# 04ddr3.net
KiCad netlist of a schematic drawn in Altium Designer
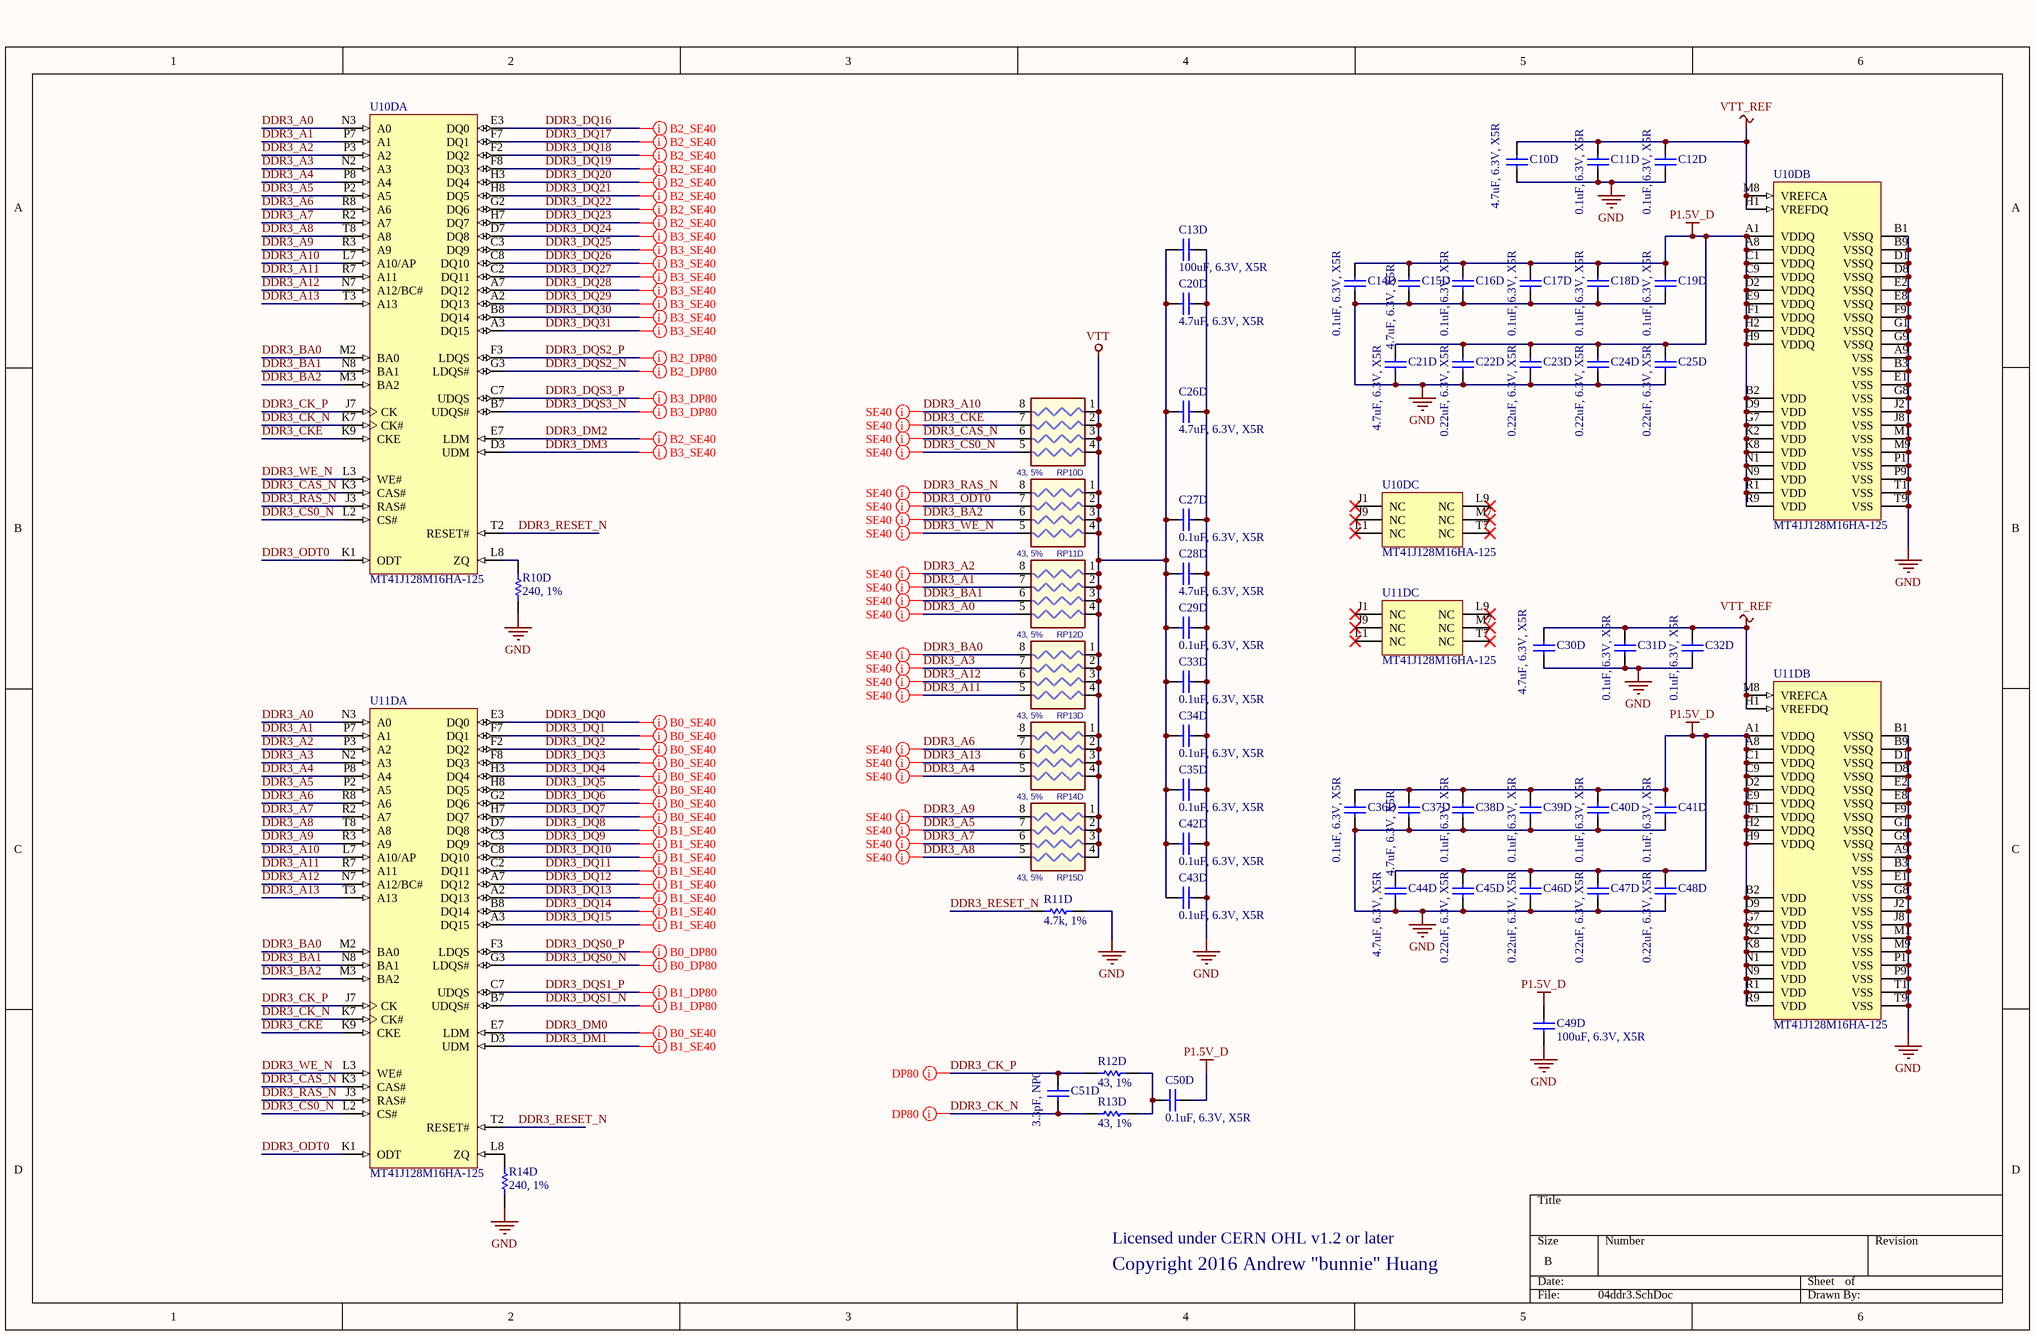
[diagram p0: 04ddr3.SchDoc]

(export (version "E")
  (design (tool "Eeschema 10.0.6"))
  (components
    (comp (ref "C10D")
      (value "4.7uF, 6.3V, X5R")
      (footprint "CAPC1005N")
      (description "Capacitor (Semiconductor SIM Model)")
      (fields (field (name "MPN") "CL05A475MQ5NQNC"))
      (libsource (lib "Miscellaneous Devices") (part "Cap Semi"))
    )
    (comp (ref "C11D")
      (value "0.1uF, 6.3V, X5R")
      (footprint "CAPC0603X03L")
      (description "Capacitor (Semiconductor SIM Model)")
      (fields (field (name "MPN") "CL03A104KQ3NNNC"))
      (libsource (lib "Miscellaneous Devices") (part "Cap Semi"))
    )
    (comp (ref "C12D")
      (value "0.1uF, 6.3V, X5R")
      (footprint "CAPC0603X03L")
      (description "Capacitor (Semiconductor SIM Model)")
      (fields (field (name "MPN") "CL03A104KQ3NNNC"))
      (libsource (lib "Miscellaneous Devices") (part "Cap Semi"))
    )
    (comp (ref "C13D")
      (value "100uF, 6.3V, X5R")
      (footprint "CAPC3216N")
      (description "Capacitor (Semiconductor SIM Model)")
      (fields (field (name "MPN") "CL31A107MQHNNNE"))
      (libsource (lib "Miscellaneous Devices") (part "Cap Semi"))
    )
    (comp (ref "C14D")
      (value "0.1uF, 6.3V, X5R")
      (footprint "CAPC0603X03L")
      (description "Capacitor (Semiconductor SIM Model)")
      (fields (field (name "MPN") "CL03A104KQ3NNNC"))
      (libsource (lib "Miscellaneous Devices") (part "Cap Semi"))
    )
    (comp (ref "C15D")
      (value "4.7uF, 6.3V, X5R")
      (footprint "CAPC1005N")
      (description "Capacitor (Semiconductor SIM Model)")
      (fields (field (name "MPN") "CL05A475MQ5NQNC"))
      (libsource (lib "Miscellaneous Devices") (part "Cap Semi"))
    )
    (comp (ref "C16D")
      (value "0.1uF, 6.3V, X5R")
      (footprint "CAPC0603X03L")
      (description "Capacitor (Semiconductor SIM Model)")
      (fields (field (name "MPN") "CL03A104KQ3NNNC"))
      (libsource (lib "Miscellaneous Devices") (part "Cap Semi"))
    )
    (comp (ref "C17D")
      (value "0.1uF, 6.3V, X5R")
      (footprint "CAPC0603X03L")
      (description "Capacitor (Semiconductor SIM Model)")
      (fields (field (name "MPN") "CL03A104KQ3NNNC"))
      (libsource (lib "Miscellaneous Devices") (part "Cap Semi"))
    )
    (comp (ref "C18D")
      (value "0.1uF, 6.3V, X5R")
      (footprint "CAPC0603X03L")
      (description "Capacitor (Semiconductor SIM Model)")
      (fields (field (name "MPN") "CL03A104KQ3NNNC"))
      (libsource (lib "Miscellaneous Devices") (part "Cap Semi"))
    )
    (comp (ref "C19D")
      (value "0.1uF, 6.3V, X5R")
      (footprint "CAPC0603X03L")
      (description "Capacitor (Semiconductor SIM Model)")
      (fields (field (name "MPN") "CL03A104KQ3NNNC"))
      (libsource (lib "Miscellaneous Devices") (part "Cap Semi"))
    )
    (comp (ref "C20D")
      (value "4.7uF, 6.3V, X5R")
      (footprint "CAPC1005N")
      (description "Capacitor (Semiconductor SIM Model)")
      (fields (field (name "MPN") "CL05A475MQ5NQNC"))
      (libsource (lib "Miscellaneous Devices") (part "Cap Semi"))
    )
    (comp (ref "C21D")
      (value "4.7uF, 6.3V, X5R")
      (footprint "CAPC1005N")
      (description "Capacitor (Semiconductor SIM Model)")
      (fields (field (name "MPN") "CL05A475MQ5NQNC"))
      (libsource (lib "Miscellaneous Devices") (part "Cap Semi"))
    )
    (comp (ref "C22D")
      (value "0.22uF, 6.3V, X5R")
      (footprint "CAPC0603X03L")
      (description "Capacitor (Semiconductor SIM Model)")
      (fields (field (name "MPN") "CL03A224MQ3NNNC"))
      (libsource (lib "Miscellaneous Devices") (part "Cap Semi"))
    )
    (comp (ref "C23D")
      (value "0.22uF, 6.3V, X5R")
      (footprint "CAPC0603X03L")
      (description "Capacitor (Semiconductor SIM Model)")
      (fields (field (name "MPN") "CL03A224MQ3NNNC"))
      (libsource (lib "Miscellaneous Devices") (part "Cap Semi"))
    )
    (comp (ref "C24D")
      (value "0.22uF, 6.3V, X5R")
      (footprint "CAPC0603X03L")
      (description "Capacitor (Semiconductor SIM Model)")
      (fields (field (name "MPN") "CL03A224MQ3NNNC"))
      (libsource (lib "Miscellaneous Devices") (part "Cap Semi"))
    )
    (comp (ref "C25D")
      (value "0.22uF, 6.3V, X5R")
      (footprint "CAPC0603X03L")
      (description "Capacitor (Semiconductor SIM Model)")
      (fields (field (name "MPN") "CL03A224MQ3NNNC"))
      (libsource (lib "Miscellaneous Devices") (part "Cap Semi"))
    )
    (comp (ref "C26D")
      (value "4.7uF, 6.3V, X5R")
      (footprint "CAPC1005N")
      (description "Capacitor (Semiconductor SIM Model)")
      (fields (field (name "MPN") "CL05A475MQ5NQNC"))
      (libsource (lib "Miscellaneous Devices") (part "Cap Semi"))
    )
    (comp (ref "C27D")
      (value "0.1uF, 6.3V, X5R")
      (footprint "CAPC0603X03L")
      (description "Capacitor (Semiconductor SIM Model)")
      (fields (field (name "MPN") "CL03A104KQ3NNNC"))
      (libsource (lib "Miscellaneous Devices") (part "Cap Semi"))
    )
    (comp (ref "C28D")
      (value "4.7uF, 6.3V, X5R")
      (footprint "CAPC1005N")
      (description "Capacitor (Semiconductor SIM Model)")
      (fields (field (name "MPN") "CL05A475MQ5NQNC"))
      (libsource (lib "Miscellaneous Devices") (part "Cap Semi"))
    )
    (comp (ref "C29D")
      (value "0.1uF, 6.3V, X5R")
      (footprint "CAPC0603X03L")
      (description "Capacitor (Semiconductor SIM Model)")
      (fields (field (name "MPN") "CL03A104KQ3NNNC"))
      (libsource (lib "Miscellaneous Devices") (part "Cap Semi"))
    )
    (comp (ref "C30D")
      (value "4.7uF, 6.3V, X5R")
      (footprint "CAPC1005N")
      (description "Capacitor (Semiconductor SIM Model)")
      (fields (field (name "MPN") "CL05A475MQ5NQNC"))
      (libsource (lib "Miscellaneous Devices") (part "Cap Semi"))
    )
    (comp (ref "C31D")
      (value "0.1uF, 6.3V, X5R")
      (footprint "CAPC0603X03L")
      (description "Capacitor (Semiconductor SIM Model)")
      (fields (field (name "MPN") "CL03A104KQ3NNNC"))
      (libsource (lib "Miscellaneous Devices") (part "Cap Semi"))
    )
    (comp (ref "C32D")
      (value "0.1uF, 6.3V, X5R")
      (footprint "CAPC0603X03L")
      (description "Capacitor (Semiconductor SIM Model)")
      (fields (field (name "MPN") "CL03A104KQ3NNNC"))
      (libsource (lib "Miscellaneous Devices") (part "Cap Semi"))
    )
    (comp (ref "C33D")
      (value "0.1uF, 6.3V, X5R")
      (footprint "CAPC0603X03L")
      (description "Capacitor (Semiconductor SIM Model)")
      (fields (field (name "MPN") "CL03A104KQ3NNNC"))
      (libsource (lib "Miscellaneous Devices") (part "Cap Semi"))
    )
    (comp (ref "C34D")
      (value "0.1uF, 6.3V, X5R")
      (footprint "CAPC0603X03L")
      (description "Capacitor (Semiconductor SIM Model)")
      (fields (field (name "MPN") "CL03A104KQ3NNNC"))
      (libsource (lib "Miscellaneous Devices") (part "Cap Semi"))
    )
    (comp (ref "C35D")
      (value "0.1uF, 6.3V, X5R")
      (footprint "CAPC0603X03L")
      (description "Capacitor (Semiconductor SIM Model)")
      (fields (field (name "MPN") "CL03A104KQ3NNNC"))
      (libsource (lib "Miscellaneous Devices") (part "Cap Semi"))
    )
    (comp (ref "C36D")
      (value "0.1uF, 6.3V, X5R")
      (footprint "CAPC0603X03L")
      (description "Capacitor (Semiconductor SIM Model)")
      (fields (field (name "MPN") "CL03A104KQ3NNNC"))
      (libsource (lib "Miscellaneous Devices") (part "Cap Semi"))
    )
    (comp (ref "C37D")
      (value "4.7uF, 6.3V, X5R")
      (footprint "CAPC1005N")
      (description "Capacitor (Semiconductor SIM Model)")
      (fields (field (name "MPN") "CL05A475MQ5NQNC"))
      (libsource (lib "Miscellaneous Devices") (part "Cap Semi"))
    )
    (comp (ref "C38D")
      (value "0.1uF, 6.3V, X5R")
      (footprint "CAPC0603X03L")
      (description "Capacitor (Semiconductor SIM Model)")
      (fields (field (name "MPN") "CL03A104KQ3NNNC"))
      (libsource (lib "Miscellaneous Devices") (part "Cap Semi"))
    )
    (comp (ref "C39D")
      (value "0.1uF, 6.3V, X5R")
      (footprint "CAPC0603X03L")
      (description "Capacitor (Semiconductor SIM Model)")
      (fields (field (name "MPN") "CL03A104KQ3NNNC"))
      (libsource (lib "Miscellaneous Devices") (part "Cap Semi"))
    )
    (comp (ref "C40D")
      (value "0.1uF, 6.3V, X5R")
      (footprint "CAPC0603X03L")
      (description "Capacitor (Semiconductor SIM Model)")
      (fields (field (name "MPN") "CL03A104KQ3NNNC"))
      (libsource (lib "Miscellaneous Devices") (part "Cap Semi"))
    )
    (comp (ref "C41D")
      (value "0.1uF, 6.3V, X5R")
      (footprint "CAPC0603X03L")
      (description "Capacitor (Semiconductor SIM Model)")
      (fields (field (name "MPN") "CL03A104KQ3NNNC"))
      (libsource (lib "Miscellaneous Devices") (part "Cap Semi"))
    )
    (comp (ref "C42D")
      (value "0.1uF, 6.3V, X5R")
      (footprint "CAPC0603X03L")
      (description "Capacitor (Semiconductor SIM Model)")
      (fields (field (name "MPN") "CL03A104KQ3NNNC"))
      (libsource (lib "Miscellaneous Devices") (part "Cap Semi"))
    )
    (comp (ref "C43D")
      (value "0.1uF, 6.3V, X5R")
      (footprint "CAPC0603X03L")
      (description "Capacitor (Semiconductor SIM Model)")
      (fields (field (name "MPN") "CL03A104KQ3NNNC"))
      (libsource (lib "Miscellaneous Devices") (part "Cap Semi"))
    )
    (comp (ref "C44D")
      (value "4.7uF, 6.3V, X5R")
      (footprint "CAPC1005N")
      (description "Capacitor (Semiconductor SIM Model)")
      (fields (field (name "MPN") "CL05A475MQ5NQNC"))
      (libsource (lib "Miscellaneous Devices") (part "Cap Semi"))
    )
    (comp (ref "C45D")
      (value "0.22uF, 6.3V, X5R")
      (footprint "CAPC0603X03L")
      (description "Capacitor (Semiconductor SIM Model)")
      (fields (field (name "MPN") "CL03A224MQ3NNNC"))
      (libsource (lib "Miscellaneous Devices") (part "Cap Semi"))
    )
    (comp (ref "C46D")
      (value "0.22uF, 6.3V, X5R")
      (footprint "CAPC0603X03L")
      (description "Capacitor (Semiconductor SIM Model)")
      (fields (field (name "MPN") "CL03A224MQ3NNNC"))
      (libsource (lib "Miscellaneous Devices") (part "Cap Semi"))
    )
    (comp (ref "C47D")
      (value "0.22uF, 6.3V, X5R")
      (footprint "CAPC0603X03L")
      (description "Capacitor (Semiconductor SIM Model)")
      (fields (field (name "MPN") "CL03A224MQ3NNNC"))
      (libsource (lib "Miscellaneous Devices") (part "Cap Semi"))
    )
    (comp (ref "C48D")
      (value "0.22uF, 6.3V, X5R")
      (footprint "CAPC0603X03L")
      (description "Capacitor (Semiconductor SIM Model)")
      (fields (field (name "MPN") "CL03A224MQ3NNNC"))
      (libsource (lib "Miscellaneous Devices") (part "Cap Semi"))
    )
    (comp (ref "C49D")
      (value "100uF, 6.3V, X5R")
      (footprint "CAPC3216N")
      (description "Capacitor (Semiconductor SIM Model)")
      (fields (field (name "MPN") "CL31A107MQHNNNE"))
      (libsource (lib "Miscellaneous Devices") (part "Cap Semi"))
    )
    (comp (ref "C50D")
      (value "0.1uF, 6.3V, X5R")
      (footprint "CAPC0603X03L")
      (description "Capacitor (Semiconductor SIM Model)")
      (fields (field (name "MPN") "CL03A104KQ3NNNC"))
      (libsource (lib "Miscellaneous Devices") (part "Cap Semi"))
    )
    (comp (ref "C51D")
      (value "3.3pF, NP0")
      (footprint "CAPC0603X03L")
      (description "Capacitor (Semiconductor SIM Model)")
      (fields (field (name "MPN") "GRM0335C1H3R3CA01D"))
      (libsource (lib "Miscellaneous Devices") (part "Cap Semi"))
    )
    (comp (ref "R10D")
      (value "240, 1%")
      (footprint "CAPC0603X03L")
      (description "Resistor")
      (fields (field (name "MPN") "ANY"))
      (libsource (lib "Miscellaneous Devices") (part "Res1"))
    )
    (comp (ref "R11D")
      (value "4.7k, 1%")
      (footprint "RESC1005N")
      (description "Resistor")
      (fields (field (name "MPN") "ANY"))
      (libsource (lib "Miscellaneous Devices") (part "Res1"))
    )
    (comp (ref "R12D")
      (value "43, 1%")
      (footprint "RESC1005N")
      (description "Resistor")
      (fields (field (name "MPN") "ANY"))
      (libsource (lib "Miscellaneous Devices") (part "Res1"))
    )
    (comp (ref "R13D")
      (value "43, 1%")
      (footprint "RESC1005N")
      (description "Resistor")
      (fields (field (name "MPN") "ANY"))
      (libsource (lib "Miscellaneous Devices") (part "Res1"))
    )
    (comp (ref "R14D")
      (value "240, 1%")
      (footprint "CAPC0603X03L")
      (description "Resistor")
      (fields (field (name "MPN") "ANY"))
      (libsource (lib "Miscellaneous Devices") (part "Res1"))
    )
    (comp (ref "RP10D")
      (value "43, 5%")
      (fields (field (name "MPN") "RP104PJ430CS"))
      (libsource (lib "*") (part "RPACK4"))
    )
    (comp (ref "RP11D")
      (value "43, 5%")
      (fields (field (name "MPN") "RP104PJ430CS"))
      (libsource (lib "*") (part "RPACK4"))
    )
    (comp (ref "RP12D")
      (value "43, 5%")
      (fields (field (name "MPN") "RP104PJ430CS"))
      (libsource (lib "*") (part "RPACK4"))
    )
    (comp (ref "RP13D")
      (value "43, 5%")
      (fields (field (name "MPN") "RP104PJ430CS"))
      (libsource (lib "*") (part "RPACK4"))
    )
    (comp (ref "RP14D")
      (value "43, 5%")
      (fields (field (name "MPN") "RP104PJ430CS"))
      (libsource (lib "*") (part "RPACK4"))
    )
    (comp (ref "RP15D")
      (value "43, 5%")
      (fields (field (name "MPN") "RP104PJ430CS"))
      (libsource (lib "*") (part "RPACK4"))
    )
    (comp (ref "U10D")
      (value "MT41J128M16HA-125")
      (footprint "MICT-HA-96")
      (description "2Gb DDR3-1600 SDRAM, 128Mb x 16, 1.25ns, 1.5V, 0 to 95 degC, 96-Ball FBGA, Pb-Free")
      (fields (field (name "VOLTAGE") "1.5V ") (field (name "MPN") "MT41J128M16JT-125:K"))
      (libsource (lib "Micron Memory DDR3 SDRAM") (part "MT41J128M16HA-125"))
    )
    (comp (ref "U11D")
      (value "MT41J128M16HA-125")
      (footprint "MICT-HA-96")
      (description "2Gb DDR3-1600 SDRAM, 128Mb x 16, 1.25ns, 1.5V, 0 to 95 degC, 96-Ball FBGA, Pb-Free")
      (fields (field (name "VOLTAGE") "1.5V ") (field (name "MPN") "MT41J128M16JT-125:K"))
      (libsource (lib "Micron Memory DDR3 SDRAM") (part "MT41J128M16HA-125"))
    )
  )
  (nets
    (net (code "1") (name "/DDR3_A0") (class "Default")
      (node (ref "RP12D") (pin "5") (pinfunction "R42_5") (pintype "passive"))
      (node (ref "U10D") (pin "N3") (pinfunction "A0_N3") (pintype "input"))
      (node (ref "U11D") (pin "N3") (pinfunction "A0_N3") (pintype "input"))
    )
    (net (code "2") (name "/DDR3_A1") (class "Default")
      (node (ref "RP12D") (pin "7") (pinfunction "R22_7") (pintype "passive"))
      (node (ref "U10D") (pin "P7") (pinfunction "A1_P7") (pintype "input"))
      (node (ref "U11D") (pin "P7") (pinfunction "A1_P7") (pintype "input"))
    )
    (net (code "3") (name "/DDR3_A2") (class "Default")
      (node (ref "RP12D") (pin "8") (pinfunction "R12_8") (pintype "passive"))
      (node (ref "U10D") (pin "P3") (pinfunction "A2_P3") (pintype "input"))
      (node (ref "U11D") (pin "P3") (pinfunction "A2_P3") (pintype "input"))
    )
    (net (code "4") (name "/DDR3_A3") (class "Default")
      (node (ref "RP13D") (pin "7") (pinfunction "R22_7") (pintype "passive"))
      (node (ref "U10D") (pin "N2") (pinfunction "A3_N2") (pintype "input"))
      (node (ref "U11D") (pin "N2") (pinfunction "A3_N2") (pintype "input"))
    )
    (net (code "5") (name "/DDR3_A4") (class "Default")
      (node (ref "RP14D") (pin "5") (pinfunction "R42_5") (pintype "passive"))
      (node (ref "U10D") (pin "P8") (pinfunction "A4_P8") (pintype "input"))
      (node (ref "U11D") (pin "P8") (pinfunction "A4_P8") (pintype "input"))
    )
    (net (code "6") (name "/DDR3_A5") (class "Default")
      (node (ref "RP15D") (pin "7") (pinfunction "R22_7") (pintype "passive"))
      (node (ref "U10D") (pin "P2") (pinfunction "A5_P2") (pintype "input"))
      (node (ref "U11D") (pin "P2") (pinfunction "A5_P2") (pintype "input"))
    )
    (net (code "7") (name "/DDR3_A6") (class "Default")
      (node (ref "RP14D") (pin "7") (pinfunction "R22_7") (pintype "passive"))
      (node (ref "U10D") (pin "R8") (pinfunction "A6_R8") (pintype "input"))
      (node (ref "U11D") (pin "R8") (pinfunction "A6_R8") (pintype "input"))
    )
    (net (code "8") (name "/DDR3_A7") (class "Default")
      (node (ref "RP15D") (pin "6") (pinfunction "R32_6") (pintype "passive"))
      (node (ref "U10D") (pin "R2") (pinfunction "A7_R2") (pintype "input"))
      (node (ref "U11D") (pin "R2") (pinfunction "A7_R2") (pintype "input"))
    )
    (net (code "9") (name "/DDR3_A8") (class "Default")
      (node (ref "RP15D") (pin "5") (pinfunction "R42_5") (pintype "passive"))
      (node (ref "U10D") (pin "T8") (pinfunction "A8_T8") (pintype "input"))
      (node (ref "U11D") (pin "T8") (pinfunction "A8_T8") (pintype "input"))
    )
    (net (code "10") (name "/DDR3_A9") (class "Default")
      (node (ref "RP15D") (pin "8") (pinfunction "R12_8") (pintype "passive"))
      (node (ref "U10D") (pin "R3") (pinfunction "A9_R3") (pintype "input"))
      (node (ref "U11D") (pin "R3") (pinfunction "A9_R3") (pintype "input"))
    )
    (net (code "11") (name "/DDR3_A10") (class "Default")
      (node (ref "RP10D") (pin "8") (pinfunction "R12_8") (pintype "passive"))
      (node (ref "U10D") (pin "L7") (pinfunction "A10/AP_L7") (pintype "input"))
      (node (ref "U11D") (pin "L7") (pinfunction "A10/AP_L7") (pintype "input"))
    )
    (net (code "12") (name "/DDR3_A11") (class "Default")
      (node (ref "RP13D") (pin "5") (pinfunction "R42_5") (pintype "passive"))
      (node (ref "U10D") (pin "R7") (pinfunction "A11_R7") (pintype "input"))
      (node (ref "U11D") (pin "R7") (pinfunction "A11_R7") (pintype "input"))
    )
    (net (code "13") (name "/DDR3_A12") (class "Default")
      (node (ref "RP13D") (pin "6") (pinfunction "R32_6") (pintype "passive"))
      (node (ref "U10D") (pin "N7") (pinfunction "A12/BC#_N7") (pintype "input"))
      (node (ref "U11D") (pin "N7") (pinfunction "A12/BC#_N7") (pintype "input"))
    )
    (net (code "14") (name "/DDR3_A13") (class "Default")
      (node (ref "RP14D") (pin "6") (pinfunction "R32_6") (pintype "passive"))
      (node (ref "U10D") (pin "T3") (pinfunction "A13_T3") (pintype "input"))
      (node (ref "U11D") (pin "T3") (pinfunction "A13_T3") (pintype "input"))
    )
    (net (code "15") (name "/DDR3_BA0") (class "Default")
      (node (ref "RP13D") (pin "8") (pinfunction "R12_8") (pintype "passive"))
      (node (ref "U10D") (pin "M2") (pinfunction "BA0_M2") (pintype "input"))
      (node (ref "U11D") (pin "M2") (pinfunction "BA0_M2") (pintype "input"))
    )
    (net (code "16") (name "/DDR3_BA1") (class "Default")
      (node (ref "RP12D") (pin "6") (pinfunction "R32_6") (pintype "passive"))
      (node (ref "U10D") (pin "N8") (pinfunction "BA1_N8") (pintype "input"))
      (node (ref "U11D") (pin "N8") (pinfunction "BA1_N8") (pintype "input"))
    )
    (net (code "17") (name "/DDR3_BA2") (class "Default")
      (node (ref "RP11D") (pin "6") (pinfunction "R32_6") (pintype "passive"))
      (node (ref "U10D") (pin "M3") (pinfunction "BA2_M3") (pintype "input"))
      (node (ref "U11D") (pin "M3") (pinfunction "BA2_M3") (pintype "input"))
    )
    (net (code "18") (name "/DDR3_CAS_N") (class "Default")
      (node (ref "RP10D") (pin "6") (pinfunction "R32_6") (pintype "passive"))
      (node (ref "U10D") (pin "K3") (pinfunction "CAS#_K3") (pintype "input"))
      (node (ref "U11D") (pin "K3") (pinfunction "CAS#_K3") (pintype "input"))
    )
    (net (code "19") (name "/DDR3_CKE") (class "Default")
      (node (ref "RP10D") (pin "7") (pinfunction "R22_7") (pintype "passive"))
      (node (ref "U10D") (pin "K9") (pinfunction "CKE_K9") (pintype "input"))
      (node (ref "U11D") (pin "K9") (pinfunction "CKE_K9") (pintype "input"))
    )
    (net (code "20") (name "/DDR3_CK_N") (class "Default")
      (node (ref "C51D") (pin "1") (pinfunction "1_1") (pintype "passive"))
      (node (ref "R13D") (pin "1") (pinfunction "1_1") (pintype "passive"))
      (node (ref "U10D") (pin "K7") (pinfunction "CK#_K7") (pintype "input"))
      (node (ref "U11D") (pin "K7") (pinfunction "CK#_K7") (pintype "input"))
    )
    (net (code "21") (name "/DDR3_CK_P") (class "Default")
      (node (ref "C51D") (pin "2") (pinfunction "2_2") (pintype "passive"))
      (node (ref "R12D") (pin "1") (pinfunction "1_1") (pintype "passive"))
      (node (ref "U10D") (pin "J7") (pinfunction "CK_J7") (pintype "input"))
      (node (ref "U11D") (pin "J7") (pinfunction "CK_J7") (pintype "input"))
    )
    (net (code "22") (name "/DDR3_CS0_N") (class "Default")
      (node (ref "RP10D") (pin "5") (pinfunction "R42_5") (pintype "passive"))
      (node (ref "U10D") (pin "L2") (pinfunction "CS#_L2") (pintype "input"))
      (node (ref "U11D") (pin "L2") (pinfunction "CS#_L2") (pintype "input"))
    )
    (net (code "23") (name "/DDR3_DM0") (class "Default")
      (node (ref "U11D") (pin "E7") (pinfunction "LDM_E7") (pintype "input"))
    )
    (net (code "24") (name "/DDR3_DM1") (class "Default")
      (node (ref "U11D") (pin "D3") (pinfunction "UDM_D3") (pintype "input"))
    )
    (net (code "25") (name "/DDR3_DM2") (class "Default")
      (node (ref "U10D") (pin "E7") (pinfunction "LDM_E7") (pintype "input"))
    )
    (net (code "26") (name "/DDR3_DM3") (class "Default")
      (node (ref "U10D") (pin "D3") (pinfunction "UDM_D3") (pintype "input"))
    )
    (net (code "27") (name "/DDR3_DQ0") (class "Default")
      (node (ref "U11D") (pin "E3") (pinfunction "DQ0_E3") (pintype "bidirectional"))
    )
    (net (code "28") (name "/DDR3_DQ1") (class "Default")
      (node (ref "U11D") (pin "F7") (pinfunction "DQ1_F7") (pintype "bidirectional"))
    )
    (net (code "29") (name "/DDR3_DQ2") (class "Default")
      (node (ref "U11D") (pin "F2") (pinfunction "DQ2_F2") (pintype "bidirectional"))
    )
    (net (code "30") (name "/DDR3_DQ3") (class "Default")
      (node (ref "U11D") (pin "F8") (pinfunction "DQ3_F8") (pintype "bidirectional"))
    )
    (net (code "31") (name "/DDR3_DQ4") (class "Default")
      (node (ref "U11D") (pin "H3") (pinfunction "DQ4_H3") (pintype "bidirectional"))
    )
    (net (code "32") (name "/DDR3_DQ5") (class "Default")
      (node (ref "U11D") (pin "H8") (pinfunction "DQ5_H8") (pintype "bidirectional"))
    )
    (net (code "33") (name "/DDR3_DQ6") (class "Default")
      (node (ref "U11D") (pin "G2") (pinfunction "DQ6_G2") (pintype "bidirectional"))
    )
    (net (code "34") (name "/DDR3_DQ7") (class "Default")
      (node (ref "U11D") (pin "H7") (pinfunction "DQ7_H7") (pintype "bidirectional"))
    )
    (net (code "35") (name "/DDR3_DQ8") (class "Default")
      (node (ref "U11D") (pin "D7") (pinfunction "DQ8_D7") (pintype "bidirectional"))
    )
    (net (code "36") (name "/DDR3_DQ9") (class "Default")
      (node (ref "U11D") (pin "C3") (pinfunction "DQ9_C3") (pintype "bidirectional"))
    )
    (net (code "37") (name "/DDR3_DQ10") (class "Default")
      (node (ref "U11D") (pin "C8") (pinfunction "DQ10_C8") (pintype "bidirectional"))
    )
    (net (code "38") (name "/DDR3_DQ11") (class "Default")
      (node (ref "U11D") (pin "C2") (pinfunction "DQ11_C2") (pintype "bidirectional"))
    )
    (net (code "39") (name "/DDR3_DQ12") (class "Default")
      (node (ref "U11D") (pin "A7") (pinfunction "DQ12_A7") (pintype "bidirectional"))
    )
    (net (code "40") (name "/DDR3_DQ13") (class "Default")
      (node (ref "U11D") (pin "A2") (pinfunction "DQ13_A2") (pintype "bidirectional"))
    )
    (net (code "41") (name "/DDR3_DQ14") (class "Default")
      (node (ref "U11D") (pin "B8") (pinfunction "DQ14_B8") (pintype "bidirectional"))
    )
    (net (code "42") (name "/DDR3_DQ15") (class "Default")
      (node (ref "U11D") (pin "A3") (pinfunction "DQ15_A3") (pintype "bidirectional"))
    )
    (net (code "43") (name "/DDR3_DQ16") (class "Default")
      (node (ref "U10D") (pin "E3") (pinfunction "DQ0_E3") (pintype "bidirectional"))
    )
    (net (code "44") (name "/DDR3_DQ17") (class "Default")
      (node (ref "U10D") (pin "F7") (pinfunction "DQ1_F7") (pintype "bidirectional"))
    )
    (net (code "45") (name "/DDR3_DQ18") (class "Default")
      (node (ref "U10D") (pin "F2") (pinfunction "DQ2_F2") (pintype "bidirectional"))
    )
    (net (code "46") (name "/DDR3_DQ19") (class "Default")
      (node (ref "U10D") (pin "F8") (pinfunction "DQ3_F8") (pintype "bidirectional"))
    )
    (net (code "47") (name "/DDR3_DQ20") (class "Default")
      (node (ref "U10D") (pin "H3") (pinfunction "DQ4_H3") (pintype "bidirectional"))
    )
    (net (code "48") (name "/DDR3_DQ21") (class "Default")
      (node (ref "U10D") (pin "H8") (pinfunction "DQ5_H8") (pintype "bidirectional"))
    )
    (net (code "49") (name "/DDR3_DQ22") (class "Default")
      (node (ref "U10D") (pin "G2") (pinfunction "DQ6_G2") (pintype "bidirectional"))
    )
    (net (code "50") (name "/DDR3_DQ23") (class "Default")
      (node (ref "U10D") (pin "H7") (pinfunction "DQ7_H7") (pintype "bidirectional"))
    )
    (net (code "51") (name "/DDR3_DQ24") (class "Default")
      (node (ref "U10D") (pin "D7") (pinfunction "DQ8_D7") (pintype "bidirectional"))
    )
    (net (code "52") (name "/DDR3_DQ25") (class "Default")
      (node (ref "U10D") (pin "C3") (pinfunction "DQ9_C3") (pintype "bidirectional"))
    )
    (net (code "53") (name "/DDR3_DQ26") (class "Default")
      (node (ref "U10D") (pin "C8") (pinfunction "DQ10_C8") (pintype "bidirectional"))
    )
    (net (code "54") (name "/DDR3_DQ27") (class "Default")
      (node (ref "U10D") (pin "C2") (pinfunction "DQ11_C2") (pintype "bidirectional"))
    )
    (net (code "55") (name "/DDR3_DQ28") (class "Default")
      (node (ref "U10D") (pin "A7") (pinfunction "DQ12_A7") (pintype "bidirectional"))
    )
    (net (code "56") (name "/DDR3_DQ29") (class "Default")
      (node (ref "U10D") (pin "A2") (pinfunction "DQ13_A2") (pintype "bidirectional"))
    )
    (net (code "57") (name "/DDR3_DQ30") (class "Default")
      (node (ref "U10D") (pin "B8") (pinfunction "DQ14_B8") (pintype "bidirectional"))
    )
    (net (code "58") (name "/DDR3_DQ31") (class "Default")
      (node (ref "U10D") (pin "A3") (pinfunction "DQ15_A3") (pintype "bidirectional"))
    )
    (net (code "59") (name "/DDR3_DQS0_N") (class "Default")
      (node (ref "U11D") (pin "G3") (pinfunction "LDQS#_G3") (pintype "bidirectional"))
    )
    (net (code "60") (name "/DDR3_DQS0_P") (class "Default")
      (node (ref "U11D") (pin "F3") (pinfunction "LDQS_F3") (pintype "bidirectional"))
    )
    (net (code "61") (name "/DDR3_DQS1_N") (class "Default")
      (node (ref "U11D") (pin "B7") (pinfunction "UDQS#_B7") (pintype "bidirectional"))
    )
    (net (code "62") (name "/DDR3_DQS1_P") (class "Default")
      (node (ref "U11D") (pin "C7") (pinfunction "UDQS_C7") (pintype "bidirectional"))
    )
    (net (code "63") (name "/DDR3_DQS2_N") (class "Default")
      (node (ref "U10D") (pin "G3") (pinfunction "LDQS#_G3") (pintype "bidirectional"))
    )
    (net (code "64") (name "/DDR3_DQS2_P") (class "Default")
      (node (ref "U10D") (pin "F3") (pinfunction "LDQS_F3") (pintype "bidirectional"))
    )
    (net (code "65") (name "/DDR3_DQS3_N") (class "Default")
      (node (ref "U10D") (pin "B7") (pinfunction "UDQS#_B7") (pintype "bidirectional"))
    )
    (net (code "66") (name "/DDR3_DQS3_P") (class "Default")
      (node (ref "U10D") (pin "C7") (pinfunction "UDQS_C7") (pintype "bidirectional"))
    )
    (net (code "67") (name "/DDR3_ODT0") (class "Default")
      (node (ref "RP11D") (pin "7") (pinfunction "R22_7") (pintype "passive"))
      (node (ref "U10D") (pin "K1") (pinfunction "ODT_K1") (pintype "input"))
      (node (ref "U11D") (pin "K1") (pinfunction "ODT_K1") (pintype "input"))
    )
    (net (code "68") (name "/DDR3_RAS_N") (class "Default")
      (node (ref "RP11D") (pin "8") (pinfunction "R12_8") (pintype "passive"))
      (node (ref "U10D") (pin "J3") (pinfunction "RAS#_J3") (pintype "input"))
      (node (ref "U11D") (pin "J3") (pinfunction "RAS#_J3") (pintype "input"))
    )
    (net (code "69") (name "/DDR3_RESET_N") (class "Default")
      (node (ref "R11D") (pin "2") (pinfunction "2_2") (pintype "passive"))
      (node (ref "U10D") (pin "T2") (pinfunction "RESET#_T2") (pintype "input"))
      (node (ref "U11D") (pin "T2") (pinfunction "RESET#_T2") (pintype "input"))
    )
    (net (code "70") (name "/DDR3_WE_N") (class "Default")
      (node (ref "RP11D") (pin "5") (pinfunction "R42_5") (pintype "passive"))
      (node (ref "U10D") (pin "L3") (pinfunction "WE#_L3") (pintype "input"))
      (node (ref "U11D") (pin "L3") (pinfunction "WE#_L3") (pintype "input"))
    )
    (net (code "71") (name "GND") (class "Default")
      (node (ref "C10D") (pin "1") (pinfunction "1_1") (pintype "passive"))
      (node (ref "C11D") (pin "2") (pinfunction "2_2") (pintype "passive"))
      (node (ref "C12D") (pin "2") (pinfunction "2_2") (pintype "passive"))
      (node (ref "C13D") (pin "2") (pinfunction "2_2") (pintype "passive"))
      (node (ref "C14D") (pin "2") (pinfunction "2_2") (pintype "passive"))
      (node (ref "C15D") (pin "2") (pinfunction "2_2") (pintype "passive"))
      (node (ref "C16D") (pin "2") (pinfunction "2_2") (pintype "passive"))
      (node (ref "C17D") (pin "2") (pinfunction "2_2") (pintype "passive"))
      (node (ref "C18D") (pin "2") (pinfunction "2_2") (pintype "passive"))
      (node (ref "C19D") (pin "2") (pinfunction "2_2") (pintype "passive"))
      (node (ref "C20D") (pin "2") (pinfunction "2_2") (pintype "passive"))
      (node (ref "C21D") (pin "2") (pinfunction "2_2") (pintype "passive"))
      (node (ref "C22D") (pin "2") (pinfunction "2_2") (pintype "passive"))
      (node (ref "C23D") (pin "2") (pinfunction "2_2") (pintype "passive"))
      (node (ref "C24D") (pin "2") (pinfunction "2_2") (pintype "passive"))
      (node (ref "C25D") (pin "2") (pinfunction "2_2") (pintype "passive"))
      (node (ref "C26D") (pin "2") (pinfunction "2_2") (pintype "passive"))
      (node (ref "C27D") (pin "1") (pinfunction "1_1") (pintype "passive"))
      (node (ref "C28D") (pin "2") (pinfunction "2_2") (pintype "passive"))
      (node (ref "C29D") (pin "1") (pinfunction "1_1") (pintype "passive"))
      (node (ref "C30D") (pin "1") (pinfunction "1_1") (pintype "passive"))
      (node (ref "C31D") (pin "2") (pinfunction "2_2") (pintype "passive"))
      (node (ref "C32D") (pin "2") (pinfunction "2_2") (pintype "passive"))
      (node (ref "C33D") (pin "1") (pinfunction "1_1") (pintype "passive"))
      (node (ref "C34D") (pin "1") (pinfunction "1_1") (pintype "passive"))
      (node (ref "C35D") (pin "1") (pinfunction "1_1") (pintype "passive"))
      (node (ref "C36D") (pin "2") (pinfunction "2_2") (pintype "passive"))
      (node (ref "C37D") (pin "2") (pinfunction "2_2") (pintype "passive"))
      (node (ref "C38D") (pin "2") (pinfunction "2_2") (pintype "passive"))
      (node (ref "C39D") (pin "2") (pinfunction "2_2") (pintype "passive"))
      (node (ref "C40D") (pin "2") (pinfunction "2_2") (pintype "passive"))
      (node (ref "C41D") (pin "2") (pinfunction "2_2") (pintype "passive"))
      (node (ref "C42D") (pin "1") (pinfunction "1_1") (pintype "passive"))
      (node (ref "C43D") (pin "1") (pinfunction "1_1") (pintype "passive"))
      (node (ref "C44D") (pin "2") (pinfunction "2_2") (pintype "passive"))
      (node (ref "C45D") (pin "2") (pinfunction "2_2") (pintype "passive"))
      (node (ref "C46D") (pin "2") (pinfunction "2_2") (pintype "passive"))
      (node (ref "C47D") (pin "2") (pinfunction "2_2") (pintype "passive"))
      (node (ref "C48D") (pin "2") (pinfunction "2_2") (pintype "passive"))
      (node (ref "C49D") (pin "1") (pinfunction "1_1") (pintype "passive"))
      (node (ref "R10D") (pin "1") (pinfunction "1_1") (pintype "passive"))
      (node (ref "R11D") (pin "1") (pinfunction "1_1") (pintype "passive"))
      (node (ref "R14D") (pin "1") (pinfunction "1_1") (pintype "passive"))
      (node (ref "U10D") (pin "A9") (pinfunction "VSS_A9") (pintype "power_in"))
      (node (ref "U10D") (pin "B1") (pinfunction "VSSQ_B1") (pintype "power_in"))
      (node (ref "U10D") (pin "B3") (pinfunction "VSS_B3") (pintype "power_in"))
      (node (ref "U10D") (pin "B9") (pinfunction "VSSQ_B9") (pintype "power_in"))
      (node (ref "U10D") (pin "D1") (pinfunction "VSSQ_D1") (pintype "power_in"))
      (node (ref "U10D") (pin "D8") (pinfunction "VSSQ_D8") (pintype "power_in"))
      (node (ref "U10D") (pin "E1") (pinfunction "VSS_E1") (pintype "power_in"))
      (node (ref "U10D") (pin "E2") (pinfunction "VSSQ_E2") (pintype "power_in"))
      (node (ref "U10D") (pin "E8") (pinfunction "VSSQ_E8") (pintype "power_in"))
      (node (ref "U10D") (pin "F9") (pinfunction "VSSQ_F9") (pintype "power_in"))
      (node (ref "U10D") (pin "G1") (pinfunction "VSSQ_G1") (pintype "power_in"))
      (node (ref "U10D") (pin "G8") (pinfunction "VSS_G8") (pintype "power_in"))
      (node (ref "U10D") (pin "G9") (pinfunction "VSSQ_G9") (pintype "power_in"))
      (node (ref "U10D") (pin "J2") (pinfunction "VSS_J2") (pintype "power_in"))
      (node (ref "U10D") (pin "J8") (pinfunction "VSS_J8") (pintype "power_in"))
      (node (ref "U10D") (pin "M1") (pinfunction "VSS_M1") (pintype "power_in"))
      (node (ref "U10D") (pin "M9") (pinfunction "VSS_M9") (pintype "power_in"))
      (node (ref "U10D") (pin "P1") (pinfunction "VSS_P1") (pintype "power_in"))
      (node (ref "U10D") (pin "P9") (pinfunction "VSS_P9") (pintype "power_in"))
      (node (ref "U10D") (pin "T1") (pinfunction "VSS_T1") (pintype "power_in"))
      (node (ref "U10D") (pin "T9") (pinfunction "VSS_T9") (pintype "power_in"))
      (node (ref "U11D") (pin "A9") (pinfunction "VSS_A9") (pintype "power_in"))
      (node (ref "U11D") (pin "B1") (pinfunction "VSSQ_B1") (pintype "power_in"))
      (node (ref "U11D") (pin "B3") (pinfunction "VSS_B3") (pintype "power_in"))
      (node (ref "U11D") (pin "B9") (pinfunction "VSSQ_B9") (pintype "power_in"))
      (node (ref "U11D") (pin "D1") (pinfunction "VSSQ_D1") (pintype "power_in"))
      (node (ref "U11D") (pin "D8") (pinfunction "VSSQ_D8") (pintype "power_in"))
      (node (ref "U11D") (pin "E1") (pinfunction "VSS_E1") (pintype "power_in"))
      (node (ref "U11D") (pin "E2") (pinfunction "VSSQ_E2") (pintype "power_in"))
      (node (ref "U11D") (pin "E8") (pinfunction "VSSQ_E8") (pintype "power_in"))
      (node (ref "U11D") (pin "F9") (pinfunction "VSSQ_F9") (pintype "power_in"))
      (node (ref "U11D") (pin "G1") (pinfunction "VSSQ_G1") (pintype "power_in"))
      (node (ref "U11D") (pin "G8") (pinfunction "VSS_G8") (pintype "power_in"))
      (node (ref "U11D") (pin "G9") (pinfunction "VSSQ_G9") (pintype "power_in"))
      (node (ref "U11D") (pin "J2") (pinfunction "VSS_J2") (pintype "power_in"))
      (node (ref "U11D") (pin "J8") (pinfunction "VSS_J8") (pintype "power_in"))
      (node (ref "U11D") (pin "M1") (pinfunction "VSS_M1") (pintype "power_in"))
      (node (ref "U11D") (pin "M9") (pinfunction "VSS_M9") (pintype "power_in"))
      (node (ref "U11D") (pin "P1") (pinfunction "VSS_P1") (pintype "power_in"))
      (node (ref "U11D") (pin "P9") (pinfunction "VSS_P9") (pintype "power_in"))
      (node (ref "U11D") (pin "T1") (pinfunction "VSS_T1") (pintype "power_in"))
      (node (ref "U11D") (pin "T9") (pinfunction "VSS_T9") (pintype "power_in"))
    )
    (net (code "72") (name "Net-(C50D-Pad2)") (class "Default")
      (node (ref "C50D") (pin "2") (pinfunction "2_2") (pintype "passive"))
      (node (ref "R12D") (pin "2") (pinfunction "2_2") (pintype "passive"))
      (node (ref "R13D") (pin "2") (pinfunction "2_2") (pintype "passive"))
    )
    (net (code "73") (name "Net-(U10DA-ZQ)") (class "Default")
      (node (ref "R10D") (pin "2") (pinfunction "2_2") (pintype "passive"))
      (node (ref "U10D") (pin "L8") (pinfunction "ZQ_L8") (pintype "input"))
    )
    (net (code "74") (name "Net-(U11DA-ZQ)") (class "Default")
      (node (ref "R14D") (pin "2") (pinfunction "2_2") (pintype "passive"))
      (node (ref "U11D") (pin "L8") (pinfunction "ZQ_L8") (pintype "input"))
    )
    (net (code "75") (name "P1.5V_D") (class "Default")
      (node (ref "C14D") (pin "1") (pinfunction "1_1") (pintype "passive"))
      (node (ref "C15D") (pin "1") (pinfunction "1_1") (pintype "passive"))
      (node (ref "C16D") (pin "1") (pinfunction "1_1") (pintype "passive"))
      (node (ref "C17D") (pin "1") (pinfunction "1_1") (pintype "passive"))
      (node (ref "C18D") (pin "1") (pinfunction "1_1") (pintype "passive"))
      (node (ref "C19D") (pin "1") (pinfunction "1_1") (pintype "passive"))
      (node (ref "C21D") (pin "1") (pinfunction "1_1") (pintype "passive"))
      (node (ref "C22D") (pin "1") (pinfunction "1_1") (pintype "passive"))
      (node (ref "C23D") (pin "1") (pinfunction "1_1") (pintype "passive"))
      (node (ref "C24D") (pin "1") (pinfunction "1_1") (pintype "passive"))
      (node (ref "C25D") (pin "1") (pinfunction "1_1") (pintype "passive"))
      (node (ref "C36D") (pin "1") (pinfunction "1_1") (pintype "passive"))
      (node (ref "C37D") (pin "1") (pinfunction "1_1") (pintype "passive"))
      (node (ref "C38D") (pin "1") (pinfunction "1_1") (pintype "passive"))
      (node (ref "C39D") (pin "1") (pinfunction "1_1") (pintype "passive"))
      (node (ref "C40D") (pin "1") (pinfunction "1_1") (pintype "passive"))
      (node (ref "C41D") (pin "1") (pinfunction "1_1") (pintype "passive"))
      (node (ref "C44D") (pin "1") (pinfunction "1_1") (pintype "passive"))
      (node (ref "C45D") (pin "1") (pinfunction "1_1") (pintype "passive"))
      (node (ref "C46D") (pin "1") (pinfunction "1_1") (pintype "passive"))
      (node (ref "C47D") (pin "1") (pinfunction "1_1") (pintype "passive"))
      (node (ref "C48D") (pin "1") (pinfunction "1_1") (pintype "passive"))
      (node (ref "C49D") (pin "2") (pinfunction "2_2") (pintype "passive"))
      (node (ref "C50D") (pin "1") (pinfunction "1_1") (pintype "passive"))
      (node (ref "U10D") (pin "A1") (pinfunction "VDDQ_A1") (pintype "power_in"))
      (node (ref "U10D") (pin "A8") (pinfunction "VDDQ_A8") (pintype "power_in"))
      (node (ref "U10D") (pin "B2") (pinfunction "VDD_B2") (pintype "power_in"))
      (node (ref "U10D") (pin "C1") (pinfunction "VDDQ_C1") (pintype "power_in"))
      (node (ref "U10D") (pin "C9") (pinfunction "VDDQ_C9") (pintype "power_in"))
      (node (ref "U10D") (pin "D2") (pinfunction "VDDQ_D2") (pintype "power_in"))
      (node (ref "U10D") (pin "D9") (pinfunction "VDD_D9") (pintype "power_in"))
      (node (ref "U10D") (pin "E9") (pinfunction "VDDQ_E9") (pintype "power_in"))
      (node (ref "U10D") (pin "F1") (pinfunction "VDDQ_F1") (pintype "power_in"))
      (node (ref "U10D") (pin "G7") (pinfunction "VDD_G7") (pintype "power_in"))
      (node (ref "U10D") (pin "H2") (pinfunction "VDDQ_H2") (pintype "power_in"))
      (node (ref "U10D") (pin "H9") (pinfunction "VDDQ_H9") (pintype "power_in"))
      (node (ref "U10D") (pin "K2") (pinfunction "VDD_K2") (pintype "power_in"))
      (node (ref "U10D") (pin "K8") (pinfunction "VDD_K8") (pintype "power_in"))
      (node (ref "U10D") (pin "N1") (pinfunction "VDD_N1") (pintype "power_in"))
      (node (ref "U10D") (pin "N9") (pinfunction "VDD_N9") (pintype "power_in"))
      (node (ref "U10D") (pin "R1") (pinfunction "VDD_R1") (pintype "power_in"))
      (node (ref "U10D") (pin "R9") (pinfunction "VDD_R9") (pintype "power_in"))
      (node (ref "U11D") (pin "A1") (pinfunction "VDDQ_A1") (pintype "power_in"))
      (node (ref "U11D") (pin "A8") (pinfunction "VDDQ_A8") (pintype "power_in"))
      (node (ref "U11D") (pin "B2") (pinfunction "VDD_B2") (pintype "power_in"))
      (node (ref "U11D") (pin "C1") (pinfunction "VDDQ_C1") (pintype "power_in"))
      (node (ref "U11D") (pin "C9") (pinfunction "VDDQ_C9") (pintype "power_in"))
      (node (ref "U11D") (pin "D2") (pinfunction "VDDQ_D2") (pintype "power_in"))
      (node (ref "U11D") (pin "D9") (pinfunction "VDD_D9") (pintype "power_in"))
      (node (ref "U11D") (pin "E9") (pinfunction "VDDQ_E9") (pintype "power_in"))
      (node (ref "U11D") (pin "F1") (pinfunction "VDDQ_F1") (pintype "power_in"))
      (node (ref "U11D") (pin "G7") (pinfunction "VDD_G7") (pintype "power_in"))
      (node (ref "U11D") (pin "H2") (pinfunction "VDDQ_H2") (pintype "power_in"))
      (node (ref "U11D") (pin "H9") (pinfunction "VDDQ_H9") (pintype "power_in"))
      (node (ref "U11D") (pin "K2") (pinfunction "VDD_K2") (pintype "power_in"))
      (node (ref "U11D") (pin "K8") (pinfunction "VDD_K8") (pintype "power_in"))
      (node (ref "U11D") (pin "N1") (pinfunction "VDD_N1") (pintype "power_in"))
      (node (ref "U11D") (pin "N9") (pinfunction "VDD_N9") (pintype "power_in"))
      (node (ref "U11D") (pin "R1") (pinfunction "VDD_R1") (pintype "power_in"))
      (node (ref "U11D") (pin "R9") (pinfunction "VDD_R9") (pintype "power_in"))
    )
    (net (code "76") (name "VTT") (class "Default")
      (node (ref "C13D") (pin "1") (pinfunction "1_1") (pintype "passive"))
      (node (ref "C20D") (pin "1") (pinfunction "1_1") (pintype "passive"))
      (node (ref "C26D") (pin "1") (pinfunction "1_1") (pintype "passive"))
      (node (ref "C27D") (pin "2") (pinfunction "2_2") (pintype "passive"))
      (node (ref "C28D") (pin "1") (pinfunction "1_1") (pintype "passive"))
      (node (ref "C29D") (pin "2") (pinfunction "2_2") (pintype "passive"))
      (node (ref "C33D") (pin "2") (pinfunction "2_2") (pintype "passive"))
      (node (ref "C34D") (pin "2") (pinfunction "2_2") (pintype "passive"))
      (node (ref "C35D") (pin "2") (pinfunction "2_2") (pintype "passive"))
      (node (ref "C42D") (pin "2") (pinfunction "2_2") (pintype "passive"))
      (node (ref "C43D") (pin "2") (pinfunction "2_2") (pintype "passive"))
      (node (ref "RP10D") (pin "1") (pinfunction "R1_1") (pintype "passive"))
      (node (ref "RP10D") (pin "2") (pinfunction "R2_2") (pintype "passive"))
      (node (ref "RP10D") (pin "3") (pinfunction "R3_3") (pintype "passive"))
      (node (ref "RP10D") (pin "4") (pinfunction "R4_4") (pintype "passive"))
      (node (ref "RP11D") (pin "1") (pinfunction "R1_1") (pintype "passive"))
      (node (ref "RP11D") (pin "2") (pinfunction "R2_2") (pintype "passive"))
      (node (ref "RP11D") (pin "3") (pinfunction "R3_3") (pintype "passive"))
      (node (ref "RP11D") (pin "4") (pinfunction "R4_4") (pintype "passive"))
      (node (ref "RP12D") (pin "1") (pinfunction "R1_1") (pintype "passive"))
      (node (ref "RP12D") (pin "2") (pinfunction "R2_2") (pintype "passive"))
      (node (ref "RP12D") (pin "3") (pinfunction "R3_3") (pintype "passive"))
      (node (ref "RP12D") (pin "4") (pinfunction "R4_4") (pintype "passive"))
      (node (ref "RP13D") (pin "1") (pinfunction "R1_1") (pintype "passive"))
      (node (ref "RP13D") (pin "2") (pinfunction "R2_2") (pintype "passive"))
      (node (ref "RP13D") (pin "3") (pinfunction "R3_3") (pintype "passive"))
      (node (ref "RP13D") (pin "4") (pinfunction "R4_4") (pintype "passive"))
      (node (ref "RP14D") (pin "1") (pinfunction "R1_1") (pintype "passive"))
      (node (ref "RP14D") (pin "2") (pinfunction "R2_2") (pintype "passive"))
      (node (ref "RP14D") (pin "3") (pinfunction "R3_3") (pintype "passive"))
      (node (ref "RP14D") (pin "4") (pinfunction "R4_4") (pintype "passive"))
      (node (ref "RP15D") (pin "1") (pinfunction "R1_1") (pintype "passive"))
      (node (ref "RP15D") (pin "2") (pinfunction "R2_2") (pintype "passive"))
      (node (ref "RP15D") (pin "3") (pinfunction "R3_3") (pintype "passive"))
      (node (ref "RP15D") (pin "4") (pinfunction "R4_4") (pintype "passive"))
    )
    (net (code "77") (name "VTT_REF") (class "Default")
      (node (ref "C10D") (pin "2") (pinfunction "2_2") (pintype "passive"))
      (node (ref "C11D") (pin "1") (pinfunction "1_1") (pintype "passive"))
      (node (ref "C12D") (pin "1") (pinfunction "1_1") (pintype "passive"))
      (node (ref "C30D") (pin "2") (pinfunction "2_2") (pintype "passive"))
      (node (ref "C31D") (pin "1") (pinfunction "1_1") (pintype "passive"))
      (node (ref "C32D") (pin "1") (pinfunction "1_1") (pintype "passive"))
      (node (ref "U10D") (pin "H1") (pinfunction "VREFDQ_H1") (pintype "input"))
      (node (ref "U10D") (pin "M8") (pinfunction "VREFCA_M8") (pintype "input"))
      (node (ref "U11D") (pin "H1") (pinfunction "VREFDQ_H1") (pintype "input"))
      (node (ref "U11D") (pin "M8") (pinfunction "VREFCA_M8") (pintype "input"))
    )
    (net (code "78") (name "unconnected-(RP14D-R12-Pad8)") (class "Default")
      (node (ref "RP14D") (pin "8") (pinfunction "R12_8") (pintype "passive"))
    )
    (net (code "79") (name "unconnected-(U10DC-NC-PadJ1)") (class "Default")
      (node (ref "U10D") (pin "J1") (pinfunction "NC_J1") (pintype "passive+no_connect"))
    )
    (net (code "80") (name "unconnected-(U10DC-NC-PadJ9)") (class "Default")
      (node (ref "U10D") (pin "J9") (pinfunction "NC_J9") (pintype "passive+no_connect"))
    )
    (net (code "81") (name "unconnected-(U10DC-NC-PadL1)") (class "Default")
      (node (ref "U10D") (pin "L1") (pinfunction "NC_L1") (pintype "passive+no_connect"))
    )
    (net (code "82") (name "unconnected-(U10DC-NC-PadL9)") (class "Default")
      (node (ref "U10D") (pin "L9") (pinfunction "NC_L9") (pintype "passive+no_connect"))
    )
    (net (code "83") (name "unconnected-(U10DC-NC-PadM7)") (class "Default")
      (node (ref "U10D") (pin "M7") (pinfunction "NC_M7") (pintype "passive+no_connect"))
    )
    (net (code "84") (name "unconnected-(U10DC-NC-PadT7)") (class "Default")
      (node (ref "U10D") (pin "T7") (pinfunction "NC_T7") (pintype "passive+no_connect"))
    )
    (net (code "85") (name "unconnected-(U11DC-NC-PadJ1)") (class "Default")
      (node (ref "U11D") (pin "J1") (pinfunction "NC_J1") (pintype "passive+no_connect"))
    )
    (net (code "86") (name "unconnected-(U11DC-NC-PadJ9)") (class "Default")
      (node (ref "U11D") (pin "J9") (pinfunction "NC_J9") (pintype "passive+no_connect"))
    )
    (net (code "87") (name "unconnected-(U11DC-NC-PadL1)") (class "Default")
      (node (ref "U11D") (pin "L1") (pinfunction "NC_L1") (pintype "passive+no_connect"))
    )
    (net (code "88") (name "unconnected-(U11DC-NC-PadL9)") (class "Default")
      (node (ref "U11D") (pin "L9") (pinfunction "NC_L9") (pintype "passive+no_connect"))
    )
    (net (code "89") (name "unconnected-(U11DC-NC-PadM7)") (class "Default")
      (node (ref "U11D") (pin "M7") (pinfunction "NC_M7") (pintype "passive+no_connect"))
    )
    (net (code "90") (name "unconnected-(U11DC-NC-PadT7)") (class "Default")
      (node (ref "U11D") (pin "T7") (pinfunction "NC_T7") (pintype "passive+no_connect"))
    )
  )
)
